# frets-main-board2_1.net
KiCad netlist of a schematic drawn in EAGLE
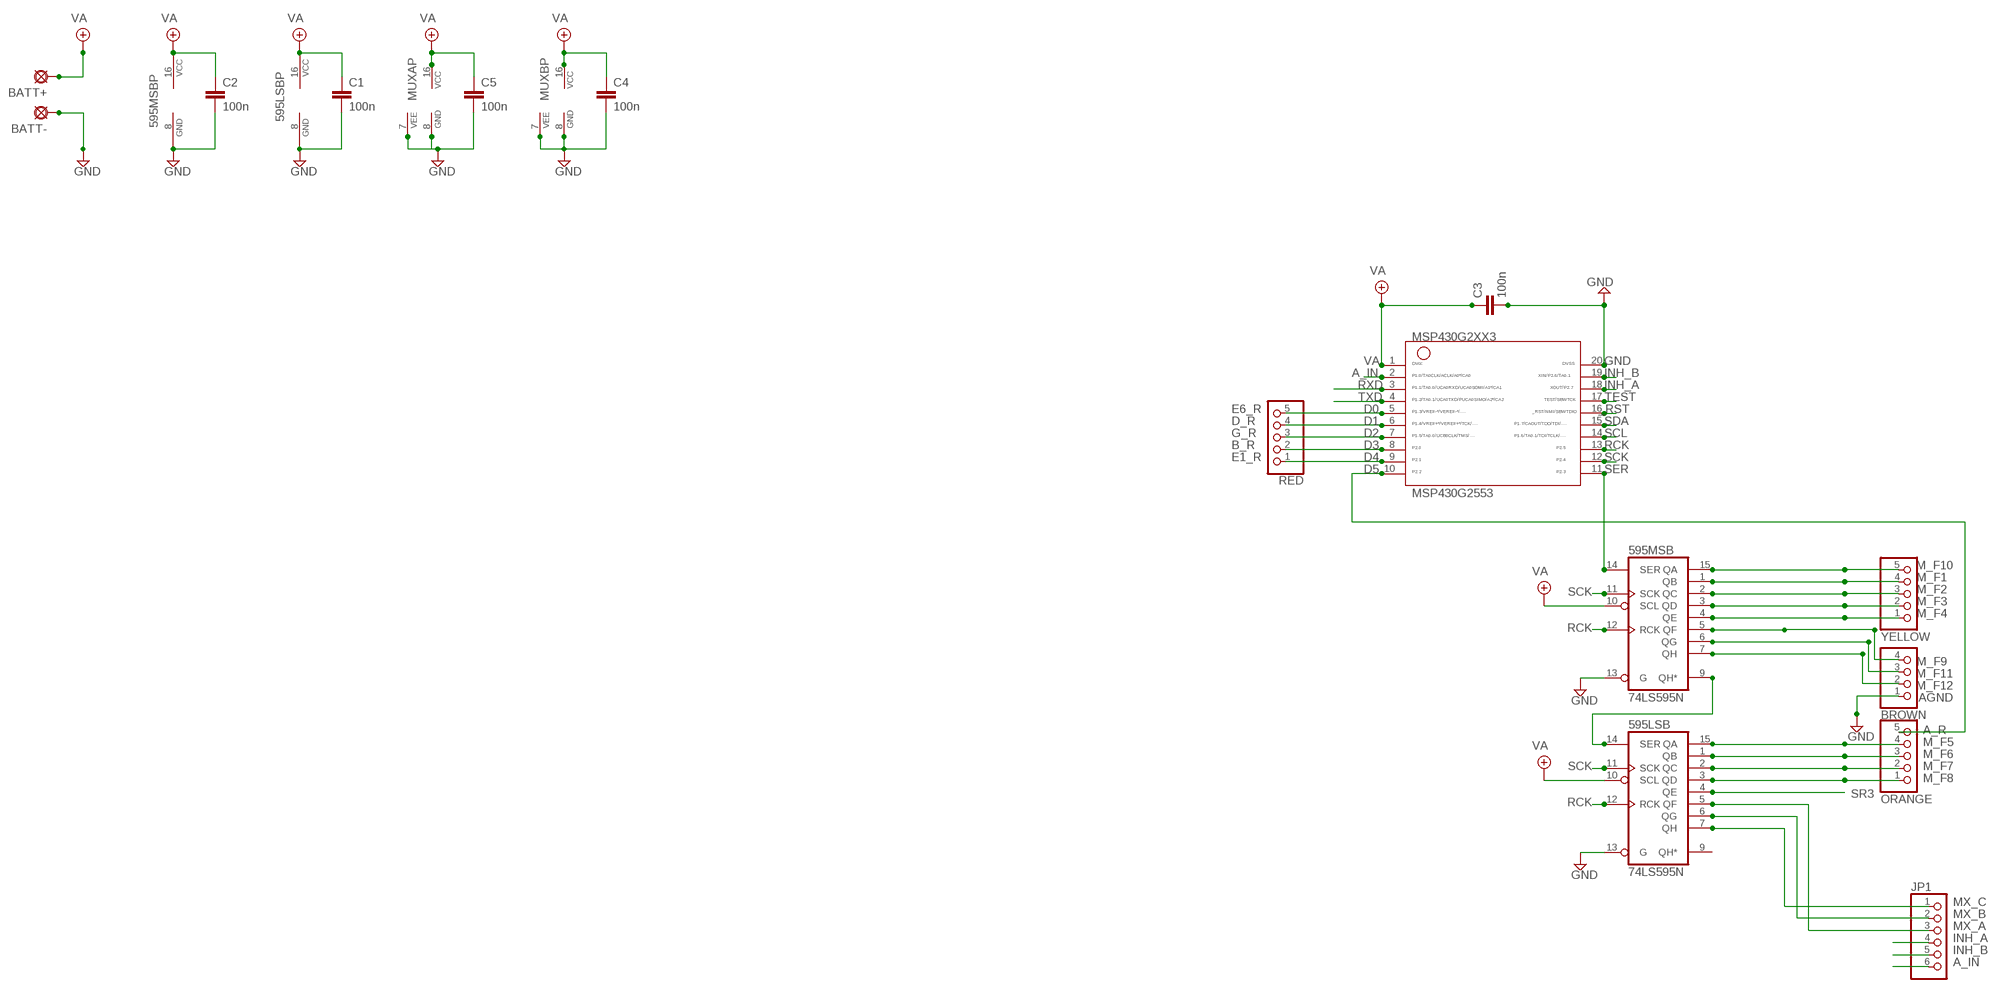
[diagram p0: schematic, sheet 1]

(export (version "E")
  (design (tool "Eeschema 10.0.6"))
  (components
    (comp (ref "595LSB")
      (value "74LS595N")
      (footprint "eagle-import:DIL16")
      (libsource (lib "eagle-import") (part "74595NLS"))
    )
    (comp (ref "595MSB")
      (value "74LS595N")
      (footprint "eagle-import:DIL16")
      (libsource (lib "eagle-import") (part "74595NLS"))
    )
    (comp (ref "BATT+")
      (value "PADL")
      (footprint "eagle-import:LONG")
      (libsource (lib "eagle-import") (part "PADL"))
    )
    (comp (ref "BATT-")
      (value "PADL")
      (footprint "eagle-import:LONG")
      (libsource (lib "eagle-import") (part "PADL"))
    )
    (comp (ref "BROWN")
      (value "PINHD-1X4")
      (footprint "eagle-import:1X04")
      (libsource (lib "eagle-import") (part "PINHD-1X4"))
    )
    (comp (ref "C1")
      (value "100n")
      (footprint "eagle-import:050X030_050_3")
      (libsource (lib "eagle-import") (part "050X030_050"))
    )
    (comp (ref "C2")
      (value "100n")
      (footprint "eagle-import:050X030_050_3")
      (libsource (lib "eagle-import") (part "050X030_050"))
    )
    (comp (ref "C3")
      (value "100n")
      (footprint "eagle-import:050X030_050_3")
      (libsource (lib "eagle-import") (part "050X030_050"))
    )
    (comp (ref "C4")
      (value "100n")
      (footprint "eagle-import:050X030_050_3")
      (libsource (lib "eagle-import") (part "050X030_050"))
    )
    (comp (ref "C5")
      (value "100n")
      (footprint "eagle-import:050X030_050_3")
      (libsource (lib "eagle-import") (part "050X030_050"))
    )
    (comp (ref "JP1")
      (value "PINHD-1X6")
      (footprint "eagle-import:1X06")
      (libsource (lib "eagle-import") (part "PINHD-1X6"))
    )
    (comp (ref "MSP430G2553")
      (value "G2XX3---N20")
      (footprint "eagle-import:N20")
      (libsource (lib "eagle-import") (part "G2XX3---N20"))
    )
    (comp (ref "MUXA")
      (value "4051N")
      (footprint "eagle-import:DIL16")
      (libsource (lib "eagle-import") (part "4051N"))
    )
    (comp (ref "MUXB")
      (value "4051N")
      (footprint "eagle-import:DIL16")
      (libsource (lib "eagle-import") (part "4051N"))
    )
    (comp (ref "ORANGE")
      (value "PINHD-1X5")
      (footprint "eagle-import:1X05")
      (libsource (lib "eagle-import") (part "PINHD-1X5"))
    )
    (comp (ref "RED")
      (value "PINHD-1X5")
      (footprint "eagle-import:1X05")
      (libsource (lib "eagle-import") (part "PINHD-1X5"))
    )
    (comp (ref "YELLOW")
      (value "PINHD-1X5")
      (footprint "eagle-import:1X05")
      (libsource (lib "eagle-import") (part "PINHD-1X5"))
    )
  )
  (nets
    (net (code "1") (name "/A_IN") (class "Default")
      (node (ref "JP1") (pin "6") (pinfunction "6_6") (pintype "passive"))
      (node (ref "MSP430G2553") (pin "2") (pinfunction "2_2") (pintype "bidirectional"))
    )
    (net (code "2") (name "/D0") (class "Default")
      (node (ref "MSP430G2553") (pin "5") (pinfunction "5_5") (pintype "bidirectional"))
      (node (ref "RED") (pin "5") (pinfunction "5_5") (pintype "passive"))
    )
    (net (code "3") (name "/D1") (class "Default")
      (node (ref "MSP430G2553") (pin "6") (pinfunction "6_6") (pintype "bidirectional"))
      (node (ref "RED") (pin "4") (pinfunction "4_4") (pintype "passive"))
    )
    (net (code "4") (name "/D2") (class "Default")
      (node (ref "MSP430G2553") (pin "7") (pinfunction "7_7") (pintype "bidirectional"))
      (node (ref "RED") (pin "3") (pinfunction "3_3") (pintype "passive"))
    )
    (net (code "5") (name "/D3") (class "Default")
      (node (ref "MSP430G2553") (pin "8") (pinfunction "8_8") (pintype "bidirectional"))
      (node (ref "RED") (pin "2") (pinfunction "2_2") (pintype "passive"))
    )
    (net (code "6") (name "/D4") (class "Default")
      (node (ref "MSP430G2553") (pin "9") (pinfunction "9_9") (pintype "bidirectional"))
      (node (ref "RED") (pin "1") (pinfunction "1_1") (pintype "passive"))
    )
    (net (code "7") (name "/D5") (class "Default")
      (node (ref "MSP430G2553") (pin "10") (pinfunction "10_10") (pintype "bidirectional"))
      (node (ref "ORANGE") (pin "5") (pinfunction "5_5") (pintype "passive"))
    )
    (net (code "8") (name "/INH_A") (class "Default")
      (node (ref "JP1") (pin "4") (pinfunction "4_4") (pintype "passive"))
      (node (ref "MSP430G2553") (pin "18") (pinfunction "18_18") (pintype "bidirectional"))
    )
    (net (code "9") (name "/INH_B") (class "Default")
      (node (ref "JP1") (pin "5") (pinfunction "5_5") (pintype "passive"))
      (node (ref "MSP430G2553") (pin "19") (pinfunction "19_19") (pintype "bidirectional"))
    )
    (net (code "10") (name "/MX_A") (class "Default")
      (node (ref "595LSB") (pin "5") (pinfunction "QF_5") (pintype "tri_state"))
      (node (ref "JP1") (pin "3") (pinfunction "3_3") (pintype "passive"))
    )
    (net (code "11") (name "/MX_B") (class "Default")
      (node (ref "595LSB") (pin "6") (pinfunction "QG_6") (pintype "tri_state"))
      (node (ref "JP1") (pin "2") (pinfunction "2_2") (pintype "passive"))
    )
    (net (code "12") (name "/MX_C") (class "Default")
      (node (ref "595LSB") (pin "7") (pinfunction "QH_7") (pintype "tri_state"))
      (node (ref "JP1") (pin "1") (pinfunction "1_1") (pintype "passive"))
    )
    (net (code "13") (name "/RCK") (class "Default")
      (node (ref "595LSB") (pin "12") (pinfunction "RCK_12") (pintype "input"))
      (node (ref "595MSB") (pin "12") (pinfunction "RCK_12") (pintype "input"))
      (node (ref "MSP430G2553") (pin "13") (pinfunction "13_13") (pintype "bidirectional"))
    )
    (net (code "14") (name "/RXD") (class "Default")
      (node (ref "MSP430G2553") (pin "3") (pinfunction "3_3") (pintype "bidirectional"))
    )
    (net (code "15") (name "/SCK") (class "Default")
      (node (ref "595LSB") (pin "11") (pinfunction "SCK_11") (pintype "input"))
      (node (ref "595MSB") (pin "11") (pinfunction "SCK_11") (pintype "input"))
      (node (ref "MSP430G2553") (pin "12") (pinfunction "12_12") (pintype "bidirectional"))
    )
    (net (code "16") (name "/SCL") (class "Default")
      (node (ref "MSP430G2553") (pin "14") (pinfunction "14_14") (pintype "bidirectional"))
    )
    (net (code "17") (name "/SDA") (class "Default")
      (node (ref "MSP430G2553") (pin "15") (pinfunction "15_15") (pintype "bidirectional"))
    )
    (net (code "18") (name "/SER") (class "Default")
      (node (ref "595MSB") (pin "14") (pinfunction "SER_14") (pintype "input"))
      (node (ref "MSP430G2553") (pin "11") (pinfunction "11_11") (pintype "bidirectional"))
    )
    (net (code "19") (name "/SR3") (class "Default")
      (node (ref "595LSB") (pin "4") (pinfunction "QE_4") (pintype "tri_state"))
    )
    (net (code "20") (name "/TEST") (class "Default")
      (node (ref "MSP430G2553") (pin "17") (pinfunction "17_17") (pintype "bidirectional"))
    )
    (net (code "21") (name "/TXD") (class "Default")
      (node (ref "MSP430G2553") (pin "4") (pinfunction "4_4") (pintype "bidirectional"))
    )
    (net (code "22") (name "/_RST") (class "Default")
      (node (ref "MSP430G2553") (pin "16") (pinfunction "16_16") (pintype "bidirectional"))
    )
    (net (code "23") (name "GND") (class "Default")
      (node (ref "595LSB") (pin "13") (pinfunction "G_13") (pintype "input"))
      (node (ref "595LSB") (pin "8") (pinfunction "GND_8") (pintype "power_in"))
      (node (ref "595MSB") (pin "13") (pinfunction "G_13") (pintype "input"))
      (node (ref "595MSB") (pin "8") (pinfunction "GND_8") (pintype "power_in"))
      (node (ref "BATT-") (pin "1") (pinfunction "PAD_1") (pintype "passive"))
      (node (ref "BROWN") (pin "1") (pinfunction "1_1") (pintype "passive"))
      (node (ref "C1") (pin "2") (pinfunction "2_2") (pintype "passive"))
      (node (ref "C2") (pin "2") (pinfunction "2_2") (pintype "passive"))
      (node (ref "C3") (pin "2") (pinfunction "2_2") (pintype "passive"))
      (node (ref "C4") (pin "2") (pinfunction "2_2") (pintype "passive"))
      (node (ref "C5") (pin "2") (pinfunction "2_2") (pintype "passive"))
      (node (ref "MSP430G2553") (pin "20") (pinfunction "20_20") (pintype "bidirectional"))
      (node (ref "MUXA") (pin "7") (pinfunction "VEE_7") (pintype "power_in"))
      (node (ref "MUXA") (pin "8") (pinfunction "GND_8") (pintype "power_in"))
      (node (ref "MUXB") (pin "7") (pinfunction "VEE_7") (pintype "power_in"))
      (node (ref "MUXB") (pin "8") (pinfunction "GND_8") (pintype "power_in"))
    )
    (net (code "24") (name "Net-(595LSBA-QA)") (class "Default")
      (node (ref "595LSB") (pin "15") (pinfunction "QA_15") (pintype "tri_state"))
      (node (ref "ORANGE") (pin "4") (pinfunction "4_4") (pintype "passive"))
    )
    (net (code "25") (name "Net-(595LSBA-QB)") (class "Default")
      (node (ref "595LSB") (pin "1") (pinfunction "QB_1") (pintype "tri_state"))
      (node (ref "ORANGE") (pin "3") (pinfunction "3_3") (pintype "passive"))
    )
    (net (code "26") (name "Net-(595LSBA-QC)") (class "Default")
      (node (ref "595LSB") (pin "2") (pinfunction "QC_2") (pintype "tri_state"))
      (node (ref "ORANGE") (pin "2") (pinfunction "2_2") (pintype "passive"))
    )
    (net (code "27") (name "Net-(595LSBA-QD)") (class "Default")
      (node (ref "595LSB") (pin "3") (pinfunction "QD_3") (pintype "tri_state"))
      (node (ref "ORANGE") (pin "1") (pinfunction "1_1") (pintype "passive"))
    )
    (net (code "28") (name "Net-(595LSBA-SER)") (class "Default")
      (node (ref "595LSB") (pin "14") (pinfunction "SER_14") (pintype "input"))
      (node (ref "595MSB") (pin "9") (pinfunction "QH*_9") (pintype "tri_state"))
    )
    (net (code "29") (name "Net-(595MSBA-QA)") (class "Default")
      (node (ref "595MSB") (pin "15") (pinfunction "QA_15") (pintype "tri_state"))
      (node (ref "YELLOW") (pin "5") (pinfunction "5_5") (pintype "passive"))
    )
    (net (code "30") (name "Net-(595MSBA-QB)") (class "Default")
      (node (ref "595MSB") (pin "1") (pinfunction "QB_1") (pintype "tri_state"))
      (node (ref "YELLOW") (pin "4") (pinfunction "4_4") (pintype "passive"))
    )
    (net (code "31") (name "Net-(595MSBA-QC)") (class "Default")
      (node (ref "595MSB") (pin "2") (pinfunction "QC_2") (pintype "tri_state"))
      (node (ref "YELLOW") (pin "3") (pinfunction "3_3") (pintype "passive"))
    )
    (net (code "32") (name "Net-(595MSBA-QD)") (class "Default")
      (node (ref "595MSB") (pin "3") (pinfunction "QD_3") (pintype "tri_state"))
      (node (ref "YELLOW") (pin "2") (pinfunction "2_2") (pintype "passive"))
    )
    (net (code "33") (name "Net-(595MSBA-QE)") (class "Default")
      (node (ref "595MSB") (pin "4") (pinfunction "QE_4") (pintype "tri_state"))
      (node (ref "YELLOW") (pin "1") (pinfunction "1_1") (pintype "passive"))
    )
    (net (code "34") (name "Net-(595MSBA-QF)") (class "Default")
      (node (ref "595MSB") (pin "5") (pinfunction "QF_5") (pintype "tri_state"))
      (node (ref "BROWN") (pin "4") (pinfunction "4_4") (pintype "passive"))
    )
    (net (code "35") (name "Net-(595MSBA-QG)") (class "Default")
      (node (ref "595MSB") (pin "6") (pinfunction "QG_6") (pintype "tri_state"))
      (node (ref "BROWN") (pin "3") (pinfunction "3_3") (pintype "passive"))
    )
    (net (code "36") (name "Net-(595MSBA-QH)") (class "Default")
      (node (ref "595MSB") (pin "7") (pinfunction "QH_7") (pintype "tri_state"))
      (node (ref "BROWN") (pin "2") (pinfunction "2_2") (pintype "passive"))
    )
    (net (code "37") (name "VA") (class "Default")
      (node (ref "595LSB") (pin "10") (pinfunction "SCL_10") (pintype "input"))
      (node (ref "595LSB") (pin "16") (pinfunction "VCC_16") (pintype "power_in"))
      (node (ref "595MSB") (pin "10") (pinfunction "SCL_10") (pintype "input"))
      (node (ref "595MSB") (pin "16") (pinfunction "VCC_16") (pintype "power_in"))
      (node (ref "BATT+") (pin "1") (pinfunction "PAD_1") (pintype "passive"))
      (node (ref "C1") (pin "1") (pinfunction "1_1") (pintype "passive"))
      (node (ref "C2") (pin "1") (pinfunction "1_1") (pintype "passive"))
      (node (ref "C3") (pin "1") (pinfunction "1_1") (pintype "passive"))
      (node (ref "C4") (pin "1") (pinfunction "1_1") (pintype "passive"))
      (node (ref "C5") (pin "1") (pinfunction "1_1") (pintype "passive"))
      (node (ref "MSP430G2553") (pin "1") (pinfunction "1_1") (pintype "bidirectional"))
      (node (ref "MUXA") (pin "16") (pinfunction "VCC_16") (pintype "power_in"))
      (node (ref "MUXB") (pin "16") (pinfunction "VCC_16") (pintype "power_in"))
    )
    (net (code "38") (name "unconnected-(595LSBA-QH*-Pad9)") (class "Default")
      (node (ref "595LSB") (pin "9") (pinfunction "QH*_9") (pintype "tri_state"))
    )
  )
)
